# v2.net
KiCad netlist of a schematic drawn in EAGLE
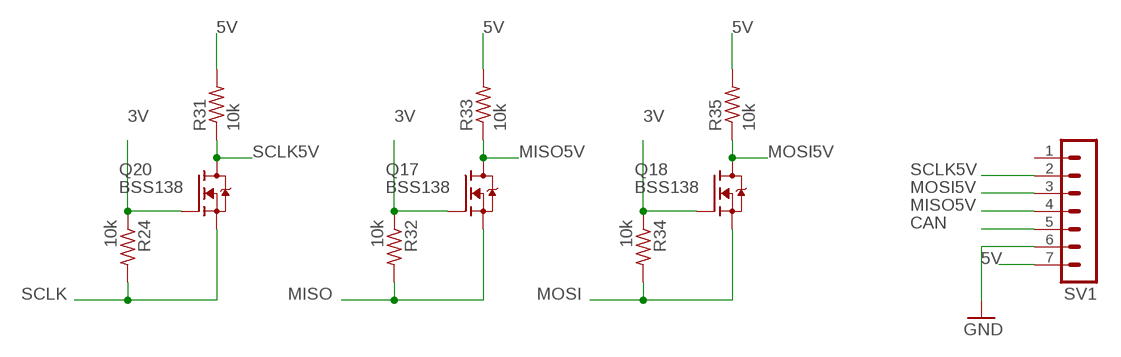
[diagram p0: schematic, sheet 1, part 1 of 2]
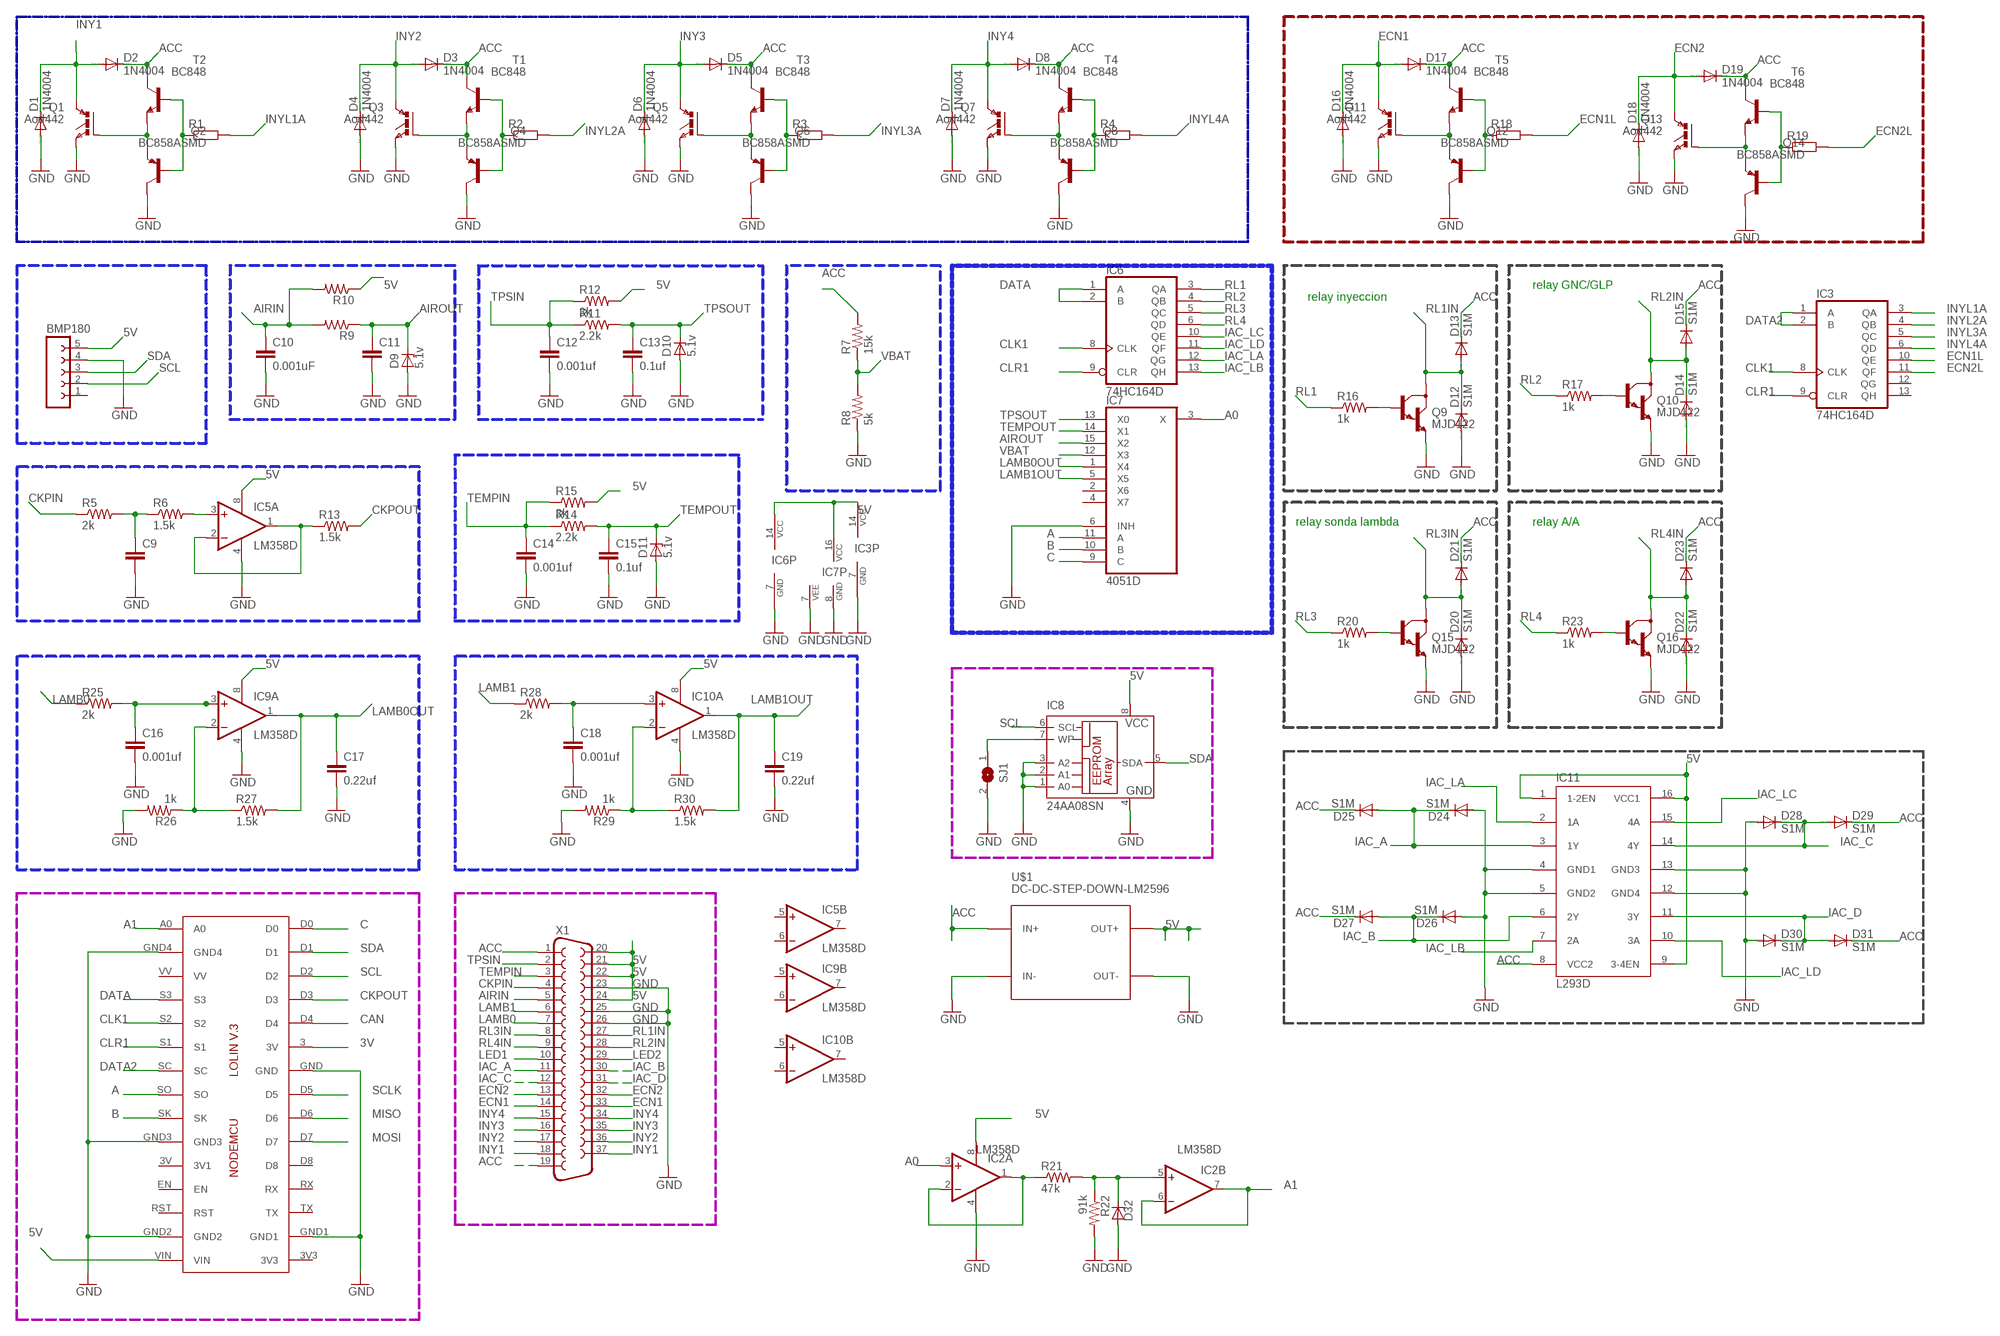
[diagram p1: schematic, sheet 1, part 2 of 2]

(export (version "E")
  (design (tool "Eeschema 10.0.6"))
  (components
    (comp (ref "BMP180")
      (value "FE05-1")
      (footprint "eagle-import:FE05-1")
      (libsource (lib "eagle-import") (part "FE05-1"))
    )
    (comp (ref "C9")
      (value "C-EU025-025X050")
      (footprint "eagle-import:C025-025X050")
      (libsource (lib "eagle-import") (part "C-EU025-025X050"))
    )
    (comp (ref "C10")
      (value "0.001uF")
      (footprint "eagle-import:C025-025X050")
      (libsource (lib "eagle-import") (part "C-EU025-025X050"))
    )
    (comp (ref "C11")
      (value "C-EU025-025X050")
      (footprint "eagle-import:C025-025X050")
      (libsource (lib "eagle-import") (part "C-EU025-025X050"))
    )
    (comp (ref "C12")
      (value "0.001uf")
      (footprint "eagle-import:C025-025X050")
      (libsource (lib "eagle-import") (part "C-EU025-025X050"))
    )
    (comp (ref "C13")
      (value "0.1uf")
      (footprint "eagle-import:C025-025X050")
      (libsource (lib "eagle-import") (part "C-EU025-025X050"))
    )
    (comp (ref "C14")
      (value "0.001uf")
      (footprint "eagle-import:C025-025X050")
      (libsource (lib "eagle-import") (part "C-EU025-025X050"))
    )
    (comp (ref "C15")
      (value "0.1uf")
      (footprint "eagle-import:C025-025X050")
      (libsource (lib "eagle-import") (part "C-EU025-025X050"))
    )
    (comp (ref "C16")
      (value "0.001uf")
      (footprint "eagle-import:C025-025X050")
      (libsource (lib "eagle-import") (part "C-EU025-025X050"))
    )
    (comp (ref "C17")
      (value "0.22uf")
      (footprint "eagle-import:C025-025X050")
      (libsource (lib "eagle-import") (part "C-EU025-025X050"))
    )
    (comp (ref "C18")
      (value "0.001uf")
      (footprint "eagle-import:C025-025X050")
      (libsource (lib "eagle-import") (part "C-EU025-025X050"))
    )
    (comp (ref "C19")
      (value "0.22uf")
      (footprint "eagle-import:C025-025X050")
      (libsource (lib "eagle-import") (part "C-EU025-025X050"))
    )
    (comp (ref "D1")
      (value "1N4004")
      (footprint "eagle-import:DO41-10")
      (libsource (lib "eagle-import") (part "1N4004"))
    )
    (comp (ref "D2")
      (value "1N4004")
      (footprint "eagle-import:DO41-10")
      (libsource (lib "eagle-import") (part "1N4004"))
    )
    (comp (ref "D3")
      (value "1N4004")
      (footprint "eagle-import:DO41-10")
      (libsource (lib "eagle-import") (part "1N4004"))
    )
    (comp (ref "D4")
      (value "1N4004")
      (footprint "eagle-import:DO41-10")
      (libsource (lib "eagle-import") (part "1N4004"))
    )
    (comp (ref "D5")
      (value "1N4004")
      (footprint "eagle-import:DO41-10")
      (libsource (lib "eagle-import") (part "1N4004"))
    )
    (comp (ref "D6")
      (value "1N4004")
      (footprint "eagle-import:DO41-10")
      (libsource (lib "eagle-import") (part "1N4004"))
    )
    (comp (ref "D7")
      (value "1N4004")
      (footprint "eagle-import:DO41-10")
      (libsource (lib "eagle-import") (part "1N4004"))
    )
    (comp (ref "D8")
      (value "1N4004")
      (footprint "eagle-import:DO41-10")
      (libsource (lib "eagle-import") (part "1N4004"))
    )
    (comp (ref "D9")
      (value "5.1v")
      (footprint "eagle-import:ZDIO-5")
      (libsource (lib "eagle-import") (part "ZENER-DIODEZD-5"))
    )
    (comp (ref "D10")
      (value "5.1v")
      (footprint "eagle-import:ZDIO-5")
      (libsource (lib "eagle-import") (part "ZENER-DIODEZD-5"))
    )
    (comp (ref "D11")
      (value "5.1v")
      (footprint "eagle-import:ZDIO-5")
      (libsource (lib "eagle-import") (part "ZENER-DIODEZD-5"))
    )
    (comp (ref "D12")
      (value "S1M")
      (footprint "eagle-import:SMA")
      (libsource (lib "eagle-import") (part "S1M"))
    )
    (comp (ref "D13")
      (value "S1M")
      (footprint "eagle-import:SMA")
      (libsource (lib "eagle-import") (part "S1M"))
    )
    (comp (ref "D14")
      (value "S1M")
      (footprint "eagle-import:SMA")
      (libsource (lib "eagle-import") (part "S1M"))
    )
    (comp (ref "D15")
      (value "S1M")
      (footprint "eagle-import:SMA")
      (libsource (lib "eagle-import") (part "S1M"))
    )
    (comp (ref "D16")
      (value "1N4004")
      (footprint "eagle-import:DO41-10")
      (libsource (lib "eagle-import") (part "1N4004"))
    )
    (comp (ref "D17")
      (value "1N4004")
      (footprint "eagle-import:DO41-10")
      (libsource (lib "eagle-import") (part "1N4004"))
    )
    (comp (ref "D18")
      (value "1N4004")
      (footprint "eagle-import:DO41-10")
      (libsource (lib "eagle-import") (part "1N4004"))
    )
    (comp (ref "D19")
      (value "1N4004")
      (footprint "eagle-import:DO41-10")
      (libsource (lib "eagle-import") (part "1N4004"))
    )
    (comp (ref "D20")
      (value "S1M")
      (footprint "eagle-import:SMA")
      (libsource (lib "eagle-import") (part "S1M"))
    )
    (comp (ref "D21")
      (value "S1M")
      (footprint "eagle-import:SMA")
      (libsource (lib "eagle-import") (part "S1M"))
    )
    (comp (ref "D22")
      (value "S1M")
      (footprint "eagle-import:SMA")
      (libsource (lib "eagle-import") (part "S1M"))
    )
    (comp (ref "D23")
      (value "S1M")
      (footprint "eagle-import:SMA")
      (libsource (lib "eagle-import") (part "S1M"))
    )
    (comp (ref "D24")
      (value "S1M")
      (footprint "eagle-import:SMA")
      (libsource (lib "eagle-import") (part "S1M"))
    )
    (comp (ref "D25")
      (value "S1M")
      (footprint "eagle-import:SMA")
      (libsource (lib "eagle-import") (part "S1M"))
    )
    (comp (ref "D26")
      (value "S1M")
      (footprint "eagle-import:SMA")
      (libsource (lib "eagle-import") (part "S1M"))
    )
    (comp (ref "D27")
      (value "S1M")
      (footprint "eagle-import:SMA")
      (libsource (lib "eagle-import") (part "S1M"))
    )
    (comp (ref "D28")
      (value "S1M")
      (footprint "eagle-import:SMA")
      (libsource (lib "eagle-import") (part "S1M"))
    )
    (comp (ref "D29")
      (value "S1M")
      (footprint "eagle-import:SMA")
      (libsource (lib "eagle-import") (part "S1M"))
    )
    (comp (ref "D30")
      (value "S1M")
      (footprint "eagle-import:SMA")
      (libsource (lib "eagle-import") (part "S1M"))
    )
    (comp (ref "D31")
      (value "S1M")
      (footprint "eagle-import:SMA")
      (libsource (lib "eagle-import") (part "S1M"))
    )
    (comp (ref "D32")
      (value "ZENER-DIODEZD-2.5")
      (footprint "eagle-import:ZDIO-2.5")
      (libsource (lib "eagle-import") (part "ZENER-DIODEZD-2.5"))
    )
    (comp (ref "IC1")
      (value "LOLINV3")
      (footprint "eagle-import:LOLINV3")
      (libsource (lib "eagle-import") (part "LOLINV3"))
    )
    (comp (ref "IC2")
      (value "LM358D")
      (footprint "eagle-import:SO08")
      (libsource (lib "eagle-import") (part "LM358D"))
    )
    (comp (ref "IC3")
      (value "74HC164D")
      (footprint "eagle-import:SO14")
      (libsource (lib "eagle-import") (part "74164DHC"))
    )
    (comp (ref "IC5")
      (value "LM358D")
      (footprint "eagle-import:SO08")
      (libsource (lib "eagle-import") (part "LM358D"))
    )
    (comp (ref "IC6")
      (value "74HC164D")
      (footprint "eagle-import:SO14")
      (libsource (lib "eagle-import") (part "74164DHC"))
    )
    (comp (ref "IC7")
      (value "4051D")
      (footprint "eagle-import:SO16")
      (libsource (lib "eagle-import") (part "4051D"))
    )
    (comp (ref "IC8")
      (value "24AA08SN")
      (footprint "eagle-import:SO-08")
      (fields (field (name "MF") "MICROCHIP") (field (name "MPN") "24AA08-I/SN"))
      (libsource (lib "eagle-import") (part "24SNAA08"))
    )
    (comp (ref "IC9")
      (value "LM358D")
      (footprint "eagle-import:SO08")
      (libsource (lib "eagle-import") (part "LM358D"))
    )
    (comp (ref "IC10")
      (value "LM358D")
      (footprint "eagle-import:SO08")
      (libsource (lib "eagle-import") (part "LM358D"))
    )
    (comp (ref "IC11")
      (value "L293D")
      (footprint "eagle-import:DIL16")
      (libsource (lib "eagle-import") (part "L293D"))
    )
    (comp (ref "Q1")
      (value "Aod442")
      (footprint "eagle-import:TO252")
      (libsource (lib "eagle-import") (part "IGBTTO252"))
    )
    (comp (ref "Q2")
      (value "BC858ASMD")
      (footprint "eagle-import:SOT23-BEC")
      (libsource (lib "eagle-import") (part "BC858SMDA"))
    )
    (comp (ref "Q3")
      (value "Aod442")
      (footprint "eagle-import:TO252")
      (libsource (lib "eagle-import") (part "IGBTTO252"))
    )
    (comp (ref "Q4")
      (value "BC858ASMD")
      (footprint "eagle-import:SOT23-BEC")
      (libsource (lib "eagle-import") (part "BC858SMDA"))
    )
    (comp (ref "Q5")
      (value "Aod442")
      (footprint "eagle-import:TO252")
      (libsource (lib "eagle-import") (part "IGBTTO252"))
    )
    (comp (ref "Q6")
      (value "BC858ASMD")
      (footprint "eagle-import:SOT23-BEC")
      (libsource (lib "eagle-import") (part "BC858SMDA"))
    )
    (comp (ref "Q7")
      (value "Aod442")
      (footprint "eagle-import:TO252")
      (libsource (lib "eagle-import") (part "IGBTTO252"))
    )
    (comp (ref "Q8")
      (value "BC858ASMD")
      (footprint "eagle-import:SOT23-BEC")
      (libsource (lib "eagle-import") (part "BC858SMDA"))
    )
    (comp (ref "Q9")
      (value "MJD122")
      (footprint "eagle-import:DPAK")
      (fields (field (name "MF") "STMicroelectronics"))
      (libsource (lib "eagle-import") (part "MJD122"))
    )
    (comp (ref "Q10")
      (value "MJD122")
      (footprint "eagle-import:DPAK")
      (fields (field (name "MF") "STMicroelectronics"))
      (libsource (lib "eagle-import") (part "MJD122"))
    )
    (comp (ref "Q11")
      (value "Aod442")
      (footprint "eagle-import:TO252")
      (libsource (lib "eagle-import") (part "IGBTTO252"))
    )
    (comp (ref "Q12")
      (value "BC858ASMD")
      (footprint "eagle-import:SOT23-BEC")
      (libsource (lib "eagle-import") (part "BC858SMDA"))
    )
    (comp (ref "Q13")
      (value "Aod442")
      (footprint "eagle-import:TO252")
      (libsource (lib "eagle-import") (part "IGBTTO252"))
    )
    (comp (ref "Q14")
      (value "BC858ASMD")
      (footprint "eagle-import:SOT23-BEC")
      (libsource (lib "eagle-import") (part "BC858SMDA"))
    )
    (comp (ref "Q15")
      (value "MJD122")
      (footprint "eagle-import:DPAK")
      (fields (field (name "MF") "STMicroelectronics"))
      (libsource (lib "eagle-import") (part "MJD122"))
    )
    (comp (ref "Q16")
      (value "MJD122")
      (footprint "eagle-import:DPAK")
      (fields (field (name "MF") "STMicroelectronics"))
      (libsource (lib "eagle-import") (part "MJD122"))
    )
    (comp (ref "Q17")
      (value "BSS138")
      (footprint "eagle-import:SOT23")
      (fields (field (name "MF") "Fairchild"))
      (libsource (lib "eagle-import") (part "BSS138"))
    )
    (comp (ref "Q18")
      (value "BSS138")
      (footprint "eagle-import:SOT23")
      (fields (field (name "MF") "Fairchild"))
      (libsource (lib "eagle-import") (part "BSS138"))
    )
    (comp (ref "Q20")
      (value "BSS138")
      (footprint "eagle-import:SOT23")
      (fields (field (name "MF") "Fairchild"))
      (libsource (lib "eagle-import") (part "BSS138"))
    )
    (comp (ref "R1")
      (value "R-EU_0204/7")
      (footprint "eagle-import:0204_7")
      (libsource (lib "eagle-import") (part "R-EU_0204/7"))
    )
    (comp (ref "R2")
      (value "R-EU_0204/7")
      (footprint "eagle-import:0204_7")
      (libsource (lib "eagle-import") (part "R-EU_0204/7"))
    )
    (comp (ref "R3")
      (value "R-EU_0204/7")
      (footprint "eagle-import:0204_7")
      (libsource (lib "eagle-import") (part "R-EU_0204/7"))
    )
    (comp (ref "R4")
      (value "R-EU_0204/7")
      (footprint "eagle-import:0204_7")
      (libsource (lib "eagle-import") (part "R-EU_0204/7"))
    )
    (comp (ref "R5")
      (value "2k")
      (footprint "eagle-import:0204_5")
      (libsource (lib "eagle-import") (part "R-US_0204/5"))
    )
    (comp (ref "R6")
      (value "1.5k")
      (footprint "eagle-import:0204_5")
      (libsource (lib "eagle-import") (part "R-US_0204/5"))
    )
    (comp (ref "R7")
      (value "15k")
      (footprint "eagle-import:0204_5")
      (libsource (lib "eagle-import") (part "R-US_0204/5"))
    )
    (comp (ref "R8")
      (value "5k")
      (footprint "eagle-import:0204_5")
      (libsource (lib "eagle-import") (part "R-US_0204/5"))
    )
    (comp (ref "R9")
      (value "R-US_0204/5")
      (footprint "eagle-import:0204_5")
      (libsource (lib "eagle-import") (part "R-US_0204/5"))
    )
    (comp (ref "R10")
      (value "R-US_0204/5")
      (footprint "eagle-import:0204_5")
      (libsource (lib "eagle-import") (part "R-US_0204/5"))
    )
    (comp (ref "R11")
      (value "2.2k")
      (footprint "eagle-import:0204_5")
      (libsource (lib "eagle-import") (part "R-US_0204/5"))
    )
    (comp (ref "R12")
      (value "3k")
      (footprint "eagle-import:0204_5")
      (libsource (lib "eagle-import") (part "R-US_0204/5"))
    )
    (comp (ref "R13")
      (value "1.5k")
      (footprint "eagle-import:0204_5")
      (libsource (lib "eagle-import") (part "R-US_0204/5"))
    )
    (comp (ref "R14")
      (value "2.2k")
      (footprint "eagle-import:0204_5")
      (libsource (lib "eagle-import") (part "R-US_0204/5"))
    )
    (comp (ref "R15")
      (value "3k")
      (footprint "eagle-import:0204_5")
      (libsource (lib "eagle-import") (part "R-US_0204/5"))
    )
    (comp (ref "R16")
      (value "1k")
      (footprint "eagle-import:0204_5")
      (libsource (lib "eagle-import") (part "R-US_0204/5"))
    )
    (comp (ref "R17")
      (value "1k")
      (footprint "eagle-import:0204_5")
      (libsource (lib "eagle-import") (part "R-US_0204/5"))
    )
    (comp (ref "R18")
      (value "R-EU_0204/7")
      (footprint "eagle-import:0204_7")
      (libsource (lib "eagle-import") (part "R-EU_0204/7"))
    )
    (comp (ref "R19")
      (value "R-EU_0204/7")
      (footprint "eagle-import:0204_7")
      (libsource (lib "eagle-import") (part "R-EU_0204/7"))
    )
    (comp (ref "R20")
      (value "1k")
      (footprint "eagle-import:0204_5")
      (libsource (lib "eagle-import") (part "R-US_0204/5"))
    )
    (comp (ref "R21")
      (value "47k")
      (footprint "eagle-import:0204_5")
      (libsource (lib "eagle-import") (part "R-US_0204/5"))
    )
    (comp (ref "R22")
      (value "91k")
      (footprint "eagle-import:0204_5")
      (libsource (lib "eagle-import") (part "R-US_0204/5"))
    )
    (comp (ref "R23")
      (value "1k")
      (footprint "eagle-import:0204_5")
      (libsource (lib "eagle-import") (part "R-US_0204/5"))
    )
    (comp (ref "R24")
      (value "10k")
      (footprint "eagle-import:0204_5")
      (libsource (lib "eagle-import") (part "R-US_0204/5"))
    )
    (comp (ref "R25")
      (value "2k")
      (footprint "eagle-import:0204_5")
      (libsource (lib "eagle-import") (part "R-US_0204/5"))
    )
    (comp (ref "R26")
      (value "1k")
      (footprint "eagle-import:0204_5")
      (libsource (lib "eagle-import") (part "R-US_0204/5"))
    )
    (comp (ref "R27")
      (value "1.5k")
      (footprint "eagle-import:0204_5")
      (libsource (lib "eagle-import") (part "R-US_0204/5"))
    )
    (comp (ref "R28")
      (value "2k")
      (footprint "eagle-import:0204_5")
      (libsource (lib "eagle-import") (part "R-US_0204/5"))
    )
    (comp (ref "R29")
      (value "1k")
      (footprint "eagle-import:0204_5")
      (libsource (lib "eagle-import") (part "R-US_0204/5"))
    )
    (comp (ref "R30")
      (value "1.5k")
      (footprint "eagle-import:0204_5")
      (libsource (lib "eagle-import") (part "R-US_0204/5"))
    )
    (comp (ref "R31")
      (value "10k")
      (footprint "eagle-import:0204_5")
      (libsource (lib "eagle-import") (part "R-US_0204/5"))
    )
    (comp (ref "R32")
      (value "10k")
      (footprint "eagle-import:0204_5")
      (libsource (lib "eagle-import") (part "R-US_0204/5"))
    )
    (comp (ref "R33")
      (value "10k")
      (footprint "eagle-import:0204_5")
      (libsource (lib "eagle-import") (part "R-US_0204/5"))
    )
    (comp (ref "R34")
      (value "10k")
      (footprint "eagle-import:0204_5")
      (libsource (lib "eagle-import") (part "R-US_0204/5"))
    )
    (comp (ref "R35")
      (value "10k")
      (footprint "eagle-import:0204_5")
      (libsource (lib "eagle-import") (part "R-US_0204/5"))
    )
    (comp (ref "SJ1")
      (value "SJW")
      (footprint "eagle-import:SJW")
      (libsource (lib "eagle-import") (part "SJW"))
    )
    (comp (ref "SV1")
      (value "MA07-1")
      (footprint "eagle-import:MA07-1")
      (libsource (lib "eagle-import") (part "MA07-1"))
    )
    (comp (ref "T1")
      (value "BC848")
      (footprint "eagle-import:SOT23")
      (libsource (lib "eagle-import") (part "BC848"))
    )
    (comp (ref "T2")
      (value "BC848")
      (footprint "eagle-import:SOT23")
      (libsource (lib "eagle-import") (part "BC848"))
    )
    (comp (ref "T3")
      (value "BC848")
      (footprint "eagle-import:SOT23")
      (libsource (lib "eagle-import") (part "BC848"))
    )
    (comp (ref "T4")
      (value "BC848")
      (footprint "eagle-import:SOT23")
      (libsource (lib "eagle-import") (part "BC848"))
    )
    (comp (ref "T5")
      (value "BC848")
      (footprint "eagle-import:SOT23")
      (libsource (lib "eagle-import") (part "BC848"))
    )
    (comp (ref "T6")
      (value "BC848")
      (footprint "eagle-import:SOT23")
      (libsource (lib "eagle-import") (part "BC848"))
    )
    (comp (ref "U$1")
      (value "DC-DC-STEP-DOWN-LM2596")
      (footprint "eagle-import:DC-DC-STEP-DOWN-LM2596")
      (libsource (lib "eagle-import") (part "DC-DC-STEP-DOWN-LM2596"))
    )
    (comp (ref "X1")
      (value "F37HP")
      (footprint "eagle-import:F37HP")
      (libsource (lib "eagle-import") (part "F37HP"))
    )
  )
  (nets
    (net (code "1") (name "/3V") (class "Default")
      (node (ref "IC1") (pin "3") (pinfunction "3V_3") (pintype "bidirectional"))
      (node (ref "Q17") (pin "1") (pinfunction "G_1") (pintype "passive"))
      (node (ref "Q18") (pin "1") (pinfunction "G_1") (pintype "passive"))
      (node (ref "Q20") (pin "1") (pinfunction "G_1") (pintype "passive"))
      (node (ref "R24") (pin "1") (pinfunction "1_1") (pintype "passive"))
      (node (ref "R32") (pin "1") (pinfunction "1_1") (pintype "passive"))
      (node (ref "R34") (pin "1") (pinfunction "1_1") (pintype "passive"))
    )
    (net (code "2") (name "/5V") (class "Default")
      (node (ref "BMP180") (pin "5") (pinfunction "5_5") (pintype "passive"))
      (node (ref "IC1") (pin "VIN") (pinfunction "VIN_VIN") (pintype "bidirectional"))
      (node (ref "IC10") (pin "8") (pinfunction "V+_8") (pintype "power_in"))
      (node (ref "IC11") (pin "1") (pinfunction "1-2EN_1") (pintype "input"))
      (node (ref "IC11") (pin "16") (pinfunction "VCC1_16") (pintype "power_in"))
      (node (ref "IC11") (pin "9") (pinfunction "3-4EN_9") (pintype "input"))
      (node (ref "IC2") (pin "8") (pinfunction "V+_8") (pintype "power_in"))
      (node (ref "IC3") (pin "14") (pinfunction "VCC_14") (pintype "power_in"))
      (node (ref "IC5") (pin "8") (pinfunction "V+_8") (pintype "power_in"))
      (node (ref "IC6") (pin "14") (pinfunction "VCC_14") (pintype "power_in"))
      (node (ref "IC7") (pin "16") (pinfunction "VCC_16") (pintype "power_in"))
      (node (ref "IC8") (pin "8") (pinfunction "VCC_8") (pintype "power_in"))
      (node (ref "IC9") (pin "8") (pinfunction "V+_8") (pintype "power_in"))
      (node (ref "R10") (pin "1") (pinfunction "1_1") (pintype "passive"))
      (node (ref "R12") (pin "2") (pinfunction "2_2") (pintype "passive"))
      (node (ref "R15") (pin "2") (pinfunction "2_2") (pintype "passive"))
      (node (ref "R31") (pin "2") (pinfunction "2_2") (pintype "passive"))
      (node (ref "R33") (pin "2") (pinfunction "2_2") (pintype "passive"))
      (node (ref "R35") (pin "2") (pinfunction "2_2") (pintype "passive"))
      (node (ref "SV1") (pin "7") (pinfunction "7_7") (pintype "passive"))
      (node (ref "U$1") (pin "OUT+") (pinfunction "OUT+_OUT+") (pintype "bidirectional"))
      (node (ref "X1") (pin "20") (pinfunction "20_20") (pintype "passive"))
      (node (ref "X1") (pin "21") (pinfunction "21_21") (pintype "passive"))
      (node (ref "X1") (pin "22") (pinfunction "22_22") (pintype "passive"))
      (node (ref "X1") (pin "24") (pinfunction "24_24") (pintype "passive"))
    )
    (net (code "3") (name "/A") (class "Default")
      (node (ref "IC1") (pin "SO") (pinfunction "SO_SO") (pintype "bidirectional"))
      (node (ref "IC7") (pin "11") (pinfunction "A_11") (pintype "input"))
    )
    (net (code "4") (name "/A0") (class "Default")
      (node (ref "IC2") (pin "3") (pinfunction "+IN_3") (pintype "input"))
      (node (ref "IC7") (pin "3") (pinfunction "X_3") (pintype "bidirectional"))
    )
    (net (code "5") (name "/A1") (class "Default")
      (node (ref "IC1") (pin "A0") (pinfunction "A0_A0") (pintype "bidirectional"))
      (node (ref "IC2") (pin "6") (pinfunction "-IN_6") (pintype "input"))
      (node (ref "IC2") (pin "7") (pinfunction "OUT_7") (pintype "output"))
    )
    (net (code "6") (name "/ACC") (class "Default")
      (node (ref "D13") (pin "C") (pinfunction "C_C") (pintype "passive"))
      (node (ref "D15") (pin "C") (pinfunction "C_C") (pintype "passive"))
      (node (ref "D17") (pin "C") (pinfunction "C_C") (pintype "passive"))
      (node (ref "D19") (pin "C") (pinfunction "C_C") (pintype "passive"))
      (node (ref "D2") (pin "C") (pinfunction "C_C") (pintype "passive"))
      (node (ref "D21") (pin "C") (pinfunction "C_C") (pintype "passive"))
      (node (ref "D23") (pin "C") (pinfunction "C_C") (pintype "passive"))
      (node (ref "D25") (pin "C") (pinfunction "C_C") (pintype "passive"))
      (node (ref "D27") (pin "C") (pinfunction "C_C") (pintype "passive"))
      (node (ref "D29") (pin "C") (pinfunction "C_C") (pintype "passive"))
      (node (ref "D3") (pin "C") (pinfunction "C_C") (pintype "passive"))
      (node (ref "D31") (pin "C") (pinfunction "C_C") (pintype "passive"))
      (node (ref "D5") (pin "C") (pinfunction "C_C") (pintype "passive"))
      (node (ref "D8") (pin "C") (pinfunction "C_C") (pintype "passive"))
      (node (ref "IC11") (pin "8") (pinfunction "VCC2_8") (pintype "power_in"))
      (node (ref "R7") (pin "2") (pinfunction "2_2") (pintype "passive"))
      (node (ref "T1") (pin "3") (pinfunction "C_3") (pintype "passive"))
      (node (ref "T2") (pin "3") (pinfunction "C_3") (pintype "passive"))
      (node (ref "T3") (pin "3") (pinfunction "C_3") (pintype "passive"))
      (node (ref "T4") (pin "3") (pinfunction "C_3") (pintype "passive"))
      (node (ref "T5") (pin "3") (pinfunction "C_3") (pintype "passive"))
      (node (ref "T6") (pin "3") (pinfunction "C_3") (pintype "passive"))
      (node (ref "U$1") (pin "IN+") (pinfunction "IN+_IN+") (pintype "bidirectional"))
      (node (ref "X1") (pin "1") (pinfunction "1_1") (pintype "passive"))
      (node (ref "X1") (pin "19") (pinfunction "19_19") (pintype "passive"))
    )
    (net (code "7") (name "/AIRIN") (class "Default")
      (node (ref "C10") (pin "1") (pinfunction "1_1") (pintype "passive"))
      (node (ref "R10") (pin "2") (pinfunction "2_2") (pintype "passive"))
      (node (ref "R9") (pin "2") (pinfunction "2_2") (pintype "passive"))
      (node (ref "X1") (pin "5") (pinfunction "5_5") (pintype "passive"))
    )
    (net (code "8") (name "/AIROUT") (class "Default")
      (node (ref "C11") (pin "1") (pinfunction "1_1") (pintype "passive"))
      (node (ref "D9") (pin "C") (pinfunction "C_C") (pintype "passive"))
      (node (ref "IC7") (pin "15") (pinfunction "X2_15") (pintype "bidirectional"))
      (node (ref "R9") (pin "1") (pinfunction "1_1") (pintype "passive"))
    )
    (net (code "9") (name "/B") (class "Default")
      (node (ref "IC1") (pin "SK") (pinfunction "SK_SK") (pintype "bidirectional"))
      (node (ref "IC7") (pin "10") (pinfunction "B_10") (pintype "input"))
    )
    (net (code "10") (name "/C") (class "Default")
      (node (ref "IC1") (pin "D0") (pinfunction "D0_D0") (pintype "bidirectional"))
      (node (ref "IC7") (pin "9") (pinfunction "C_9") (pintype "input"))
    )
    (net (code "11") (name "/CAN") (class "Default")
      (node (ref "IC1") (pin "D4") (pinfunction "D4_D4") (pintype "bidirectional"))
      (node (ref "SV1") (pin "5") (pinfunction "5_5") (pintype "passive"))
    )
    (net (code "12") (name "/CKPIN") (class "Default")
      (node (ref "R5") (pin "1") (pinfunction "1_1") (pintype "passive"))
      (node (ref "X1") (pin "4") (pinfunction "4_4") (pintype "passive"))
    )
    (net (code "13") (name "/CKPOUT") (class "Default")
      (node (ref "IC1") (pin "D3") (pinfunction "D3_D3") (pintype "bidirectional"))
      (node (ref "R13") (pin "2") (pinfunction "2_2") (pintype "passive"))
    )
    (net (code "14") (name "/CLK1") (class "Default")
      (node (ref "IC1") (pin "S2") (pinfunction "S2_S2") (pintype "bidirectional"))
      (node (ref "IC3") (pin "8") (pinfunction "CLK_8") (pintype "input"))
      (node (ref "IC6") (pin "8") (pinfunction "CLK_8") (pintype "input"))
    )
    (net (code "15") (name "/CLR1") (class "Default")
      (node (ref "IC1") (pin "S1") (pinfunction "S1_S1") (pintype "bidirectional"))
      (node (ref "IC3") (pin "9") (pinfunction "CLR_9") (pintype "input"))
      (node (ref "IC6") (pin "9") (pinfunction "CLR_9") (pintype "input"))
    )
    (net (code "16") (name "/DATA") (class "Default")
      (node (ref "IC1") (pin "S3") (pinfunction "S3_S3") (pintype "bidirectional"))
      (node (ref "IC6") (pin "1") (pinfunction "A_1") (pintype "input"))
      (node (ref "IC6") (pin "2") (pinfunction "B_2") (pintype "input"))
    )
    (net (code "17") (name "/DATA2") (class "Default")
      (node (ref "IC1") (pin "SC") (pinfunction "SC_SC") (pintype "bidirectional"))
      (node (ref "IC3") (pin "1") (pinfunction "A_1") (pintype "input"))
      (node (ref "IC3") (pin "2") (pinfunction "B_2") (pintype "input"))
    )
    (net (code "18") (name "/ECN1") (class "Default")
      (node (ref "D16") (pin "C") (pinfunction "C_C") (pintype "passive"))
      (node (ref "D17") (pin "A") (pinfunction "A_A") (pintype "passive"))
      (node (ref "Q11") (pin "2") (pinfunction "C_2") (pintype "passive"))
      (node (ref "X1") (pin "14") (pinfunction "14_14") (pintype "passive"))
      (node (ref "X1") (pin "33") (pinfunction "33_33") (pintype "passive"))
    )
    (net (code "19") (name "/ECN1L") (class "Default")
      (node (ref "IC3") (pin "10") (pinfunction "QE_10") (pintype "output"))
      (node (ref "R18") (pin "2") (pinfunction "2_2") (pintype "passive"))
    )
    (net (code "20") (name "/ECN2") (class "Default")
      (node (ref "D18") (pin "C") (pinfunction "C_C") (pintype "passive"))
      (node (ref "D19") (pin "A") (pinfunction "A_A") (pintype "passive"))
      (node (ref "Q13") (pin "2") (pinfunction "C_2") (pintype "passive"))
      (node (ref "X1") (pin "13") (pinfunction "13_13") (pintype "passive"))
      (node (ref "X1") (pin "32") (pinfunction "32_32") (pintype "passive"))
    )
    (net (code "21") (name "/ECN2L") (class "Default")
      (node (ref "IC3") (pin "11") (pinfunction "QF_11") (pintype "output"))
      (node (ref "R19") (pin "2") (pinfunction "2_2") (pintype "passive"))
    )
    (net (code "22") (name "/IAC_A") (class "Default")
      (node (ref "D24") (pin "C") (pinfunction "C_C") (pintype "passive"))
      (node (ref "D25") (pin "A") (pinfunction "A_A") (pintype "passive"))
      (node (ref "IC11") (pin "3") (pinfunction "1Y_3") (pintype "output"))
      (node (ref "X1") (pin "11") (pinfunction "11_11") (pintype "passive"))
    )
    (net (code "23") (name "/IAC_B") (class "Default")
      (node (ref "D26") (pin "C") (pinfunction "C_C") (pintype "passive"))
      (node (ref "D27") (pin "A") (pinfunction "A_A") (pintype "passive"))
      (node (ref "IC11") (pin "6") (pinfunction "2Y_6") (pintype "output"))
      (node (ref "X1") (pin "30") (pinfunction "30_30") (pintype "passive"))
    )
    (net (code "24") (name "/IAC_C") (class "Default")
      (node (ref "D28") (pin "C") (pinfunction "C_C") (pintype "passive"))
      (node (ref "D29") (pin "A") (pinfunction "A_A") (pintype "passive"))
      (node (ref "IC11") (pin "14") (pinfunction "4Y_14") (pintype "output"))
      (node (ref "X1") (pin "12") (pinfunction "12_12") (pintype "passive"))
    )
    (net (code "25") (name "/IAC_D") (class "Default")
      (node (ref "D30") (pin "C") (pinfunction "C_C") (pintype "passive"))
      (node (ref "D31") (pin "A") (pinfunction "A_A") (pintype "passive"))
      (node (ref "IC11") (pin "11") (pinfunction "3Y_11") (pintype "output"))
      (node (ref "X1") (pin "31") (pinfunction "31_31") (pintype "passive"))
    )
    (net (code "26") (name "/IAC_LA") (class "Default")
      (node (ref "IC11") (pin "2") (pinfunction "1A_2") (pintype "input"))
      (node (ref "IC6") (pin "12") (pinfunction "QG_12") (pintype "output"))
    )
    (net (code "27") (name "/IAC_LB") (class "Default")
      (node (ref "IC11") (pin "7") (pinfunction "2A_7") (pintype "input"))
      (node (ref "IC6") (pin "13") (pinfunction "QH_13") (pintype "output"))
    )
    (net (code "28") (name "/IAC_LC") (class "Default")
      (node (ref "IC11") (pin "15") (pinfunction "4A_15") (pintype "input"))
      (node (ref "IC6") (pin "10") (pinfunction "QE_10") (pintype "output"))
    )
    (net (code "29") (name "/IAC_LD") (class "Default")
      (node (ref "IC11") (pin "10") (pinfunction "3A_10") (pintype "input"))
      (node (ref "IC6") (pin "11") (pinfunction "QF_11") (pintype "output"))
    )
    (net (code "30") (name "/INY1") (class "Default")
      (node (ref "D1") (pin "C") (pinfunction "C_C") (pintype "passive"))
      (node (ref "D2") (pin "A") (pinfunction "A_A") (pintype "passive"))
      (node (ref "Q1") (pin "2") (pinfunction "C_2") (pintype "passive"))
      (node (ref "X1") (pin "18") (pinfunction "18_18") (pintype "passive"))
      (node (ref "X1") (pin "37") (pinfunction "37_37") (pintype "passive"))
    )
    (net (code "31") (name "/INY2") (class "Default")
      (node (ref "D3") (pin "A") (pinfunction "A_A") (pintype "passive"))
      (node (ref "D4") (pin "C") (pinfunction "C_C") (pintype "passive"))
      (node (ref "Q3") (pin "2") (pinfunction "C_2") (pintype "passive"))
      (node (ref "X1") (pin "17") (pinfunction "17_17") (pintype "passive"))
      (node (ref "X1") (pin "36") (pinfunction "36_36") (pintype "passive"))
    )
    (net (code "32") (name "/INY3") (class "Default")
      (node (ref "D5") (pin "A") (pinfunction "A_A") (pintype "passive"))
      (node (ref "D6") (pin "C") (pinfunction "C_C") (pintype "passive"))
      (node (ref "Q5") (pin "2") (pinfunction "C_2") (pintype "passive"))
      (node (ref "X1") (pin "16") (pinfunction "16_16") (pintype "passive"))
      (node (ref "X1") (pin "35") (pinfunction "35_35") (pintype "passive"))
    )
    (net (code "33") (name "/INY4") (class "Default")
      (node (ref "D7") (pin "C") (pinfunction "C_C") (pintype "passive"))
      (node (ref "D8") (pin "A") (pinfunction "A_A") (pintype "passive"))
      (node (ref "Q7") (pin "2") (pinfunction "C_2") (pintype "passive"))
      (node (ref "X1") (pin "15") (pinfunction "15_15") (pintype "passive"))
      (node (ref "X1") (pin "34") (pinfunction "34_34") (pintype "passive"))
    )
    (net (code "34") (name "/INYL1A") (class "Default")
      (node (ref "IC3") (pin "3") (pinfunction "QA_3") (pintype "output"))
      (node (ref "R1") (pin "2") (pinfunction "2_2") (pintype "passive"))
    )
    (net (code "35") (name "/INYL2A") (class "Default")
      (node (ref "IC3") (pin "4") (pinfunction "QB_4") (pintype "output"))
      (node (ref "R2") (pin "2") (pinfunction "2_2") (pintype "passive"))
    )
    (net (code "36") (name "/INYL3A") (class "Default")
      (node (ref "IC3") (pin "5") (pinfunction "QC_5") (pintype "output"))
      (node (ref "R3") (pin "2") (pinfunction "2_2") (pintype "passive"))
    )
    (net (code "37") (name "/INYL4A") (class "Default")
      (node (ref "IC3") (pin "6") (pinfunction "QD_6") (pintype "output"))
      (node (ref "R4") (pin "2") (pinfunction "2_2") (pintype "passive"))
    )
    (net (code "38") (name "/LAMB0") (class "Default")
      (node (ref "R25") (pin "1") (pinfunction "1_1") (pintype "passive"))
      (node (ref "X1") (pin "7") (pinfunction "7_7") (pintype "passive"))
    )
    (net (code "39") (name "/LAMB0OUT") (class "Default")
      (node (ref "C17") (pin "1") (pinfunction "1_1") (pintype "passive"))
      (node (ref "IC7") (pin "1") (pinfunction "X4_1") (pintype "bidirectional"))
      (node (ref "IC9") (pin "1") (pinfunction "OUT_1") (pintype "output"))
      (node (ref "R27") (pin "2") (pinfunction "2_2") (pintype "passive"))
    )
    (net (code "40") (name "/LAMB1") (class "Default")
      (node (ref "R28") (pin "1") (pinfunction "1_1") (pintype "passive"))
      (node (ref "X1") (pin "6") (pinfunction "6_6") (pintype "passive"))
    )
    (net (code "41") (name "/LAMB1OUT") (class "Default")
      (node (ref "C19") (pin "1") (pinfunction "1_1") (pintype "passive"))
      (node (ref "IC10") (pin "1") (pinfunction "OUT_1") (pintype "output"))
      (node (ref "IC7") (pin "5") (pinfunction "X5_5") (pintype "bidirectional"))
      (node (ref "R30") (pin "2") (pinfunction "2_2") (pintype "passive"))
    )
    (net (code "42") (name "/LED1") (class "Default")
      (node (ref "X1") (pin "10") (pinfunction "10_10") (pintype "passive"))
    )
    (net (code "43") (name "/LED2") (class "Default")
      (node (ref "X1") (pin "29") (pinfunction "29_29") (pintype "passive"))
    )
    (net (code "44") (name "/MISO") (class "Default")
      (node (ref "IC1") (pin "D6") (pinfunction "D6_D6") (pintype "bidirectional"))
      (node (ref "Q17") (pin "2") (pinfunction "S_2") (pintype "passive"))
      (node (ref "R32") (pin "2") (pinfunction "2_2") (pintype "passive"))
    )
    (net (code "45") (name "/MISO5V") (class "Default")
      (node (ref "Q17") (pin "3") (pinfunction "D_3") (pintype "passive"))
      (node (ref "R33") (pin "1") (pinfunction "1_1") (pintype "passive"))
      (node (ref "SV1") (pin "4") (pinfunction "4_4") (pintype "passive"))
    )
    (net (code "46") (name "/MOSI") (class "Default")
      (node (ref "IC1") (pin "D7") (pinfunction "D7_D7") (pintype "bidirectional"))
      (node (ref "Q18") (pin "2") (pinfunction "S_2") (pintype "passive"))
      (node (ref "R34") (pin "2") (pinfunction "2_2") (pintype "passive"))
    )
    (net (code "47") (name "/MOSI5V") (class "Default")
      (node (ref "Q18") (pin "3") (pinfunction "D_3") (pintype "passive"))
      (node (ref "R35") (pin "1") (pinfunction "1_1") (pintype "passive"))
      (node (ref "SV1") (pin "3") (pinfunction "3_3") (pintype "passive"))
    )
    (net (code "48") (name "/RL1") (class "Default")
      (node (ref "IC6") (pin "3") (pinfunction "QA_3") (pintype "output"))
      (node (ref "R16") (pin "1") (pinfunction "1_1") (pintype "passive"))
    )
    (net (code "49") (name "/RL1IN") (class "Default")
      (node (ref "D12") (pin "C") (pinfunction "C_C") (pintype "passive"))
      (node (ref "D13") (pin "A") (pinfunction "A_A") (pintype "passive"))
      (node (ref "Q9") (pin "4") (pinfunction "C_4") (pintype "passive"))
      (node (ref "X1") (pin "27") (pinfunction "27_27") (pintype "passive"))
    )
    (net (code "50") (name "/RL2") (class "Default")
      (node (ref "IC6") (pin "4") (pinfunction "QB_4") (pintype "output"))
      (node (ref "R17") (pin "1") (pinfunction "1_1") (pintype "passive"))
    )
    (net (code "51") (name "/RL2IN") (class "Default")
      (node (ref "D14") (pin "C") (pinfunction "C_C") (pintype "passive"))
      (node (ref "D15") (pin "A") (pinfunction "A_A") (pintype "passive"))
      (node (ref "Q10") (pin "4") (pinfunction "C_4") (pintype "passive"))
      (node (ref "X1") (pin "28") (pinfunction "28_28") (pintype "passive"))
    )
    (net (code "52") (name "/RL3") (class "Default")
      (node (ref "IC6") (pin "5") (pinfunction "QC_5") (pintype "output"))
      (node (ref "R20") (pin "1") (pinfunction "1_1") (pintype "passive"))
    )
    (net (code "53") (name "/RL3IN") (class "Default")
      (node (ref "D20") (pin "C") (pinfunction "C_C") (pintype "passive"))
      (node (ref "D21") (pin "A") (pinfunction "A_A") (pintype "passive"))
      (node (ref "Q15") (pin "4") (pinfunction "C_4") (pintype "passive"))
      (node (ref "X1") (pin "8") (pinfunction "8_8") (pintype "passive"))
    )
    (net (code "54") (name "/RL4") (class "Default")
      (node (ref "IC6") (pin "6") (pinfunction "QD_6") (pintype "output"))
      (node (ref "R23") (pin "1") (pinfunction "1_1") (pintype "passive"))
    )
    (net (code "55") (name "/RL4IN") (class "Default")
      (node (ref "D22") (pin "C") (pinfunction "C_C") (pintype "passive"))
      (node (ref "D23") (pin "A") (pinfunction "A_A") (pintype "passive"))
      (node (ref "Q16") (pin "4") (pinfunction "C_4") (pintype "passive"))
      (node (ref "X1") (pin "9") (pinfunction "9_9") (pintype "passive"))
    )
    (net (code "56") (name "/SCL") (class "Default")
      (node (ref "BMP180") (pin "2") (pinfunction "2_2") (pintype "passive"))
      (node (ref "IC1") (pin "D2") (pinfunction "D2_D2") (pintype "bidirectional"))
      (node (ref "IC8") (pin "6") (pinfunction "SCL_6") (pintype "input"))
    )
    (net (code "57") (name "/SCLK") (class "Default")
      (node (ref "IC1") (pin "D5") (pinfunction "D5_D5") (pintype "bidirectional"))
      (node (ref "Q20") (pin "2") (pinfunction "S_2") (pintype "passive"))
      (node (ref "R24") (pin "2") (pinfunction "2_2") (pintype "passive"))
    )
    (net (code "58") (name "/SCLK5V") (class "Default")
      (node (ref "Q20") (pin "3") (pinfunction "D_3") (pintype "passive"))
      (node (ref "R31") (pin "1") (pinfunction "1_1") (pintype "passive"))
      (node (ref "SV1") (pin "2") (pinfunction "2_2") (pintype "passive"))
    )
    (net (code "59") (name "/SDA") (class "Default")
      (node (ref "BMP180") (pin "3") (pinfunction "3_3") (pintype "passive"))
      (node (ref "IC1") (pin "D1") (pinfunction "D1_D1") (pintype "bidirectional"))
      (node (ref "IC8") (pin "5") (pinfunction "SDA_5") (pintype "bidirectional"))
    )
    (net (code "60") (name "/TEMPIN") (class "Default")
      (node (ref "C14") (pin "1") (pinfunction "1_1") (pintype "passive"))
      (node (ref "R14") (pin "1") (pinfunction "1_1") (pintype "passive"))
      (node (ref "R15") (pin "1") (pinfunction "1_1") (pintype "passive"))
      (node (ref "X1") (pin "3") (pinfunction "3_3") (pintype "passive"))
    )
    (net (code "61") (name "/TEMPOUT") (class "Default")
      (node (ref "C15") (pin "1") (pinfunction "1_1") (pintype "passive"))
      (node (ref "D11") (pin "C") (pinfunction "C_C") (pintype "passive"))
      (node (ref "IC7") (pin "14") (pinfunction "X1_14") (pintype "bidirectional"))
      (node (ref "R14") (pin "2") (pinfunction "2_2") (pintype "passive"))
    )
    (net (code "62") (name "/TPSIN") (class "Default")
      (node (ref "C12") (pin "1") (pinfunction "1_1") (pintype "passive"))
      (node (ref "R11") (pin "1") (pinfunction "1_1") (pintype "passive"))
      (node (ref "R12") (pin "1") (pinfunction "1_1") (pintype "passive"))
      (node (ref "X1") (pin "2") (pinfunction "2_2") (pintype "passive"))
    )
    (net (code "63") (name "/TPSOUT") (class "Default")
      (node (ref "C13") (pin "1") (pinfunction "1_1") (pintype "passive"))
      (node (ref "D10") (pin "C") (pinfunction "C_C") (pintype "passive"))
      (node (ref "IC7") (pin "13") (pinfunction "X0_13") (pintype "bidirectional"))
      (node (ref "R11") (pin "2") (pinfunction "2_2") (pintype "passive"))
    )
    (net (code "64") (name "/VBAT") (class "Default")
      (node (ref "IC7") (pin "12") (pinfunction "X3_12") (pintype "bidirectional"))
      (node (ref "R7") (pin "1") (pinfunction "1_1") (pintype "passive"))
      (node (ref "R8") (pin "2") (pinfunction "2_2") (pintype "passive"))
    )
    (net (code "65") (name "GND") (class "Default")
      (node (ref "BMP180") (pin "4") (pinfunction "4_4") (pintype "passive"))
      (node (ref "C10") (pin "2") (pinfunction "2_2") (pintype "passive"))
      (node (ref "C11") (pin "2") (pinfunction "2_2") (pintype "passive"))
      (node (ref "C12") (pin "2") (pinfunction "2_2") (pintype "passive"))
      (node (ref "C13") (pin "2") (pinfunction "2_2") (pintype "passive"))
      (node (ref "C14") (pin "2") (pinfunction "2_2") (pintype "passive"))
      (node (ref "C15") (pin "2") (pinfunction "2_2") (pintype "passive"))
      (node (ref "C16") (pin "2") (pinfunction "2_2") (pintype "passive"))
      (node (ref "C17") (pin "2") (pinfunction "2_2") (pintype "passive"))
      (node (ref "C18") (pin "2") (pinfunction "2_2") (pintype "passive"))
      (node (ref "C19") (pin "2") (pinfunction "2_2") (pintype "passive"))
      (node (ref "C9") (pin "2") (pinfunction "2_2") (pintype "passive"))
      (node (ref "D1") (pin "A") (pinfunction "A_A") (pintype "passive"))
      (node (ref "D10") (pin "A") (pinfunction "A_A") (pintype "passive"))
      (node (ref "D11") (pin "A") (pinfunction "A_A") (pintype "passive"))
      (node (ref "D12") (pin "A") (pinfunction "A_A") (pintype "passive"))
      (node (ref "D14") (pin "A") (pinfunction "A_A") (pintype "passive"))
      (node (ref "D16") (pin "A") (pinfunction "A_A") (pintype "passive"))
      (node (ref "D18") (pin "A") (pinfunction "A_A") (pintype "passive"))
      (node (ref "D20") (pin "A") (pinfunction "A_A") (pintype "passive"))
      (node (ref "D22") (pin "A") (pinfunction "A_A") (pintype "passive"))
      (node (ref "D24") (pin "A") (pinfunction "A_A") (pintype "passive"))
      (node (ref "D26") (pin "A") (pinfunction "A_A") (pintype "passive"))
      (node (ref "D28") (pin "A") (pinfunction "A_A") (pintype "passive"))
      (node (ref "D30") (pin "A") (pinfunction "A_A") (pintype "passive"))
      (node (ref "D32") (pin "A") (pinfunction "A_A") (pintype "passive"))
      (node (ref "D4") (pin "A") (pinfunction "A_A") (pintype "passive"))
      (node (ref "D6") (pin "A") (pinfunction "A_A") (pintype "passive"))
      (node (ref "D7") (pin "A") (pinfunction "A_A") (pintype "passive"))
      (node (ref "D9") (pin "A") (pinfunction "A_A") (pintype "passive"))
      (node (ref "IC1") (pin "GND") (pinfunction "GND_GND") (pintype "bidirectional"))
      (node (ref "IC1") (pin "GND1") (pinfunction "GND1_GND1") (pintype "bidirectional"))
      (node (ref "IC1") (pin "GND2") (pinfunction "GND2_GND2") (pintype "bidirectional"))
      (node (ref "IC1") (pin "GND3") (pinfunction "GND3_GND3") (pintype "bidirectional"))
      (node (ref "IC1") (pin "GND4") (pinfunction "GND4_GND4") (pintype "bidirectional"))
      (node (ref "IC10") (pin "4") (pinfunction "V-_4") (pintype "power_in"))
      (node (ref "IC11") (pin "12") (pinfunction "GND4_12") (pintype "power_in"))
      (node (ref "IC11") (pin "13") (pinfunction "GND3_13") (pintype "power_in"))
      (node (ref "IC11") (pin "4") (pinfunction "GND1_4") (pintype "power_in"))
      (node (ref "IC11") (pin "5") (pinfunction "GND2_5") (pintype "power_in"))
      (node (ref "IC2") (pin "4") (pinfunction "V-_4") (pintype "power_in"))
      (node (ref "IC3") (pin "7") (pinfunction "GND_7") (pintype "power_in"))
      (node (ref "IC5") (pin "4") (pinfunction "V-_4") (pintype "power_in"))
      (node (ref "IC6") (pin "7") (pinfunction "GND_7") (pintype "power_in"))
      (node (ref "IC7") (pin "6") (pinfunction "INH_6") (pintype "input"))
      (node (ref "IC7") (pin "7") (pinfunction "VEE_7") (pintype "power_in"))
      (node (ref "IC7") (pin "8") (pinfunction "GND_8") (pintype "power_in"))
      (node (ref "IC8") (pin "1") (pinfunction "A0_1") (pintype "input"))
      (node (ref "IC8") (pin "2") (pinfunction "A1_2") (pintype "input"))
      (node (ref "IC8") (pin "3") (pinfunction "A2_3") (pintype "input"))
      (node (ref "IC8") (pin "4") (pinfunction "GND_4") (pintype "power_in"))
      (node (ref "IC9") (pin "4") (pinfunction "V-_4") (pintype "power_in"))
      (node (ref "Q1") (pin "3") (pinfunction "E_3") (pintype "passive"))
      (node (ref "Q10") (pin "3") (pinfunction "E_3") (pintype "passive"))
      (node (ref "Q11") (pin "3") (pinfunction "E_3") (pintype "passive"))
      (node (ref "Q12") (pin "C") (pinfunction "C_C") (pintype "passive"))
      (node (ref "Q13") (pin "3") (pinfunction "E_3") (pintype "passive"))
      (node (ref "Q14") (pin "C") (pinfunction "C_C") (pintype "passive"))
      (node (ref "Q15") (pin "3") (pinfunction "E_3") (pintype "passive"))
      (node (ref "Q16") (pin "3") (pinfunction "E_3") (pintype "passive"))
      (node (ref "Q2") (pin "C") (pinfunction "C_C") (pintype "passive"))
      (node (ref "Q3") (pin "3") (pinfunction "E_3") (pintype "passive"))
      (node (ref "Q4") (pin "C") (pinfunction "C_C") (pintype "passive"))
      (node (ref "Q5") (pin "3") (pinfunction "E_3") (pintype "passive"))
      (node (ref "Q6") (pin "C") (pinfunction "C_C") (pintype "passive"))
      (node (ref "Q7") (pin "3") (pinfunction "E_3") (pintype "passive"))
      (node (ref "Q8") (pin "C") (pinfunction "C_C") (pintype "passive"))
      (node (ref "Q9") (pin "3") (pinfunction "E_3") (pintype "passive"))
      (node (ref "R22") (pin "2") (pinfunction "2_2") (pintype "passive"))
      (node (ref "R26") (pin "2") (pinfunction "2_2") (pintype "passive"))
      (node (ref "R29") (pin "2") (pinfunction "2_2") (pintype "passive"))
      (node (ref "R8") (pin "1") (pinfunction "1_1") (pintype "passive"))
      (node (ref "SJ1") (pin "2") (pinfunction "2_2") (pintype "passive"))
      (node (ref "SV1") (pin "6") (pinfunction "6_6") (pintype "passive"))
      (node (ref "U$1") (pin "IN-") (pinfunction "IN-_IN-") (pintype "bidirectional"))
      (node (ref "U$1") (pin "OUT-") (pinfunction "OUT-_OUT-") (pintype "bidirectional"))
      (node (ref "X1") (pin "23") (pinfunction "23_23") (pintype "passive"))
      (node (ref "X1") (pin "25") (pinfunction "25_25") (pintype "passive"))
      (node (ref "X1") (pin "26") (pinfunction "26_26") (pintype "passive"))
    )
    (net (code "66") (name "Net-(C9-Pad1)") (class "Default")
      (node (ref "C9") (pin "1") (pinfunction "1_1") (pintype "passive"))
      (node (ref "R5") (pin "2") (pinfunction "2_2") (pintype "passive"))
      (node (ref "R6") (pin "1") (pinfunction "1_1") (pintype "passive"))
    )
    (net (code "67") (name "Net-(IC2A--IN)") (class "Default")
      (node (ref "IC2") (pin "1") (pinfunction "OUT_1") (pintype "output"))
      (node (ref "IC2") (pin "2") (pinfunction "-IN_2") (pintype "input"))
      (node (ref "R21") (pin "1") (pinfunction "1_1") (pintype "passive"))
    )
    (net (code "68") (name "Net-(IC2B-+IN)") (class "Default")
      (node (ref "D32") (pin "C") (pinfunction "C_C") (pintype "passive"))
      (node (ref "IC2") (pin "5") (pinfunction "+IN_5") (pintype "input"))
      (node (ref "R21") (pin "2") (pinfunction "2_2") (pintype "passive"))
      (node (ref "R22") (pin "1") (pinfunction "1_1") (pintype "passive"))
    )
    (net (code "69") (name "Net-(IC5A-+IN)") (class "Default")
      (node (ref "IC5") (pin "3") (pinfunction "+IN_3") (pintype "input"))
      (node (ref "R6") (pin "2") (pinfunction "2_2") (pintype "passive"))
    )
    (net (code "70") (name "Net-(IC5A--IN)") (class "Default")
      (node (ref "IC5") (pin "1") (pinfunction "OUT_1") (pintype "output"))
      (node (ref "IC5") (pin "2") (pinfunction "-IN_2") (pintype "input"))
      (node (ref "R13") (pin "1") (pinfunction "1_1") (pintype "passive"))
    )
    (net (code "71") (name "Net-(IC8-WP)") (class "Default")
      (node (ref "IC8") (pin "7") (pinfunction "WP_7") (pintype "input"))
      (node (ref "SJ1") (pin "1") (pinfunction "1_1") (pintype "passive"))
    )
    (net (code "72") (name "Net-(IC9A-+IN)") (class "Default")
      (node (ref "C16") (pin "1") (pinfunction "1_1") (pintype "passive"))
      (node (ref "IC9") (pin "3") (pinfunction "+IN_3") (pintype "input"))
      (node (ref "R25") (pin "2") (pinfunction "2_2") (pintype "passive"))
    )
    (net (code "73") (name "Net-(IC9A--IN)") (class "Default")
      (node (ref "IC9") (pin "2") (pinfunction "-IN_2") (pintype "input"))
      (node (ref "R26") (pin "1") (pinfunction "1_1") (pintype "passive"))
      (node (ref "R27") (pin "1") (pinfunction "1_1") (pintype "passive"))
    )
    (net (code "74") (name "Net-(IC10A-+IN)") (class "Default")
      (node (ref "C18") (pin "1") (pinfunction "1_1") (pintype "passive"))
      (node (ref "IC10") (pin "3") (pinfunction "+IN_3") (pintype "input"))
      (node (ref "R28") (pin "2") (pinfunction "2_2") (pintype "passive"))
    )
    (net (code "75") (name "Net-(IC10A--IN)") (class "Default")
      (node (ref "IC10") (pin "2") (pinfunction "-IN_2") (pintype "input"))
      (node (ref "R29") (pin "1") (pinfunction "1_1") (pintype "passive"))
      (node (ref "R30") (pin "1") (pinfunction "1_1") (pintype "passive"))
    )
    (net (code "76") (name "Net-(Q1-G)") (class "Default")
      (node (ref "Q1") (pin "1") (pinfunction "G_1") (pintype "passive"))
      (node (ref "Q2") (pin "E") (pinfunction "E_E") (pintype "passive"))
      (node (ref "T2") (pin "2") (pinfunction "E_2") (pintype "passive"))
    )
    (net (code "77") (name "Net-(Q3-G)") (class "Default")
      (node (ref "Q3") (pin "1") (pinfunction "G_1") (pintype "passive"))
      (node (ref "Q4") (pin "E") (pinfunction "E_E") (pintype "passive"))
      (node (ref "T1") (pin "2") (pinfunction "E_2") (pintype "passive"))
    )
    (net (code "78") (name "Net-(Q5-G)") (class "Default")
      (node (ref "Q5") (pin "1") (pinfunction "G_1") (pintype "passive"))
      (node (ref "Q6") (pin "E") (pinfunction "E_E") (pintype "passive"))
      (node (ref "T3") (pin "2") (pinfunction "E_2") (pintype "passive"))
    )
    (net (code "79") (name "Net-(Q7-G)") (class "Default")
      (node (ref "Q7") (pin "1") (pinfunction "G_1") (pintype "passive"))
      (node (ref "Q8") (pin "E") (pinfunction "E_E") (pintype "passive"))
      (node (ref "T4") (pin "2") (pinfunction "E_2") (pintype "passive"))
    )
    (net (code "80") (name "Net-(Q9-B)") (class "Default")
      (node (ref "Q9") (pin "1") (pinfunction "B_1") (pintype "passive"))
      (node (ref "R16") (pin "2") (pinfunction "2_2") (pintype "passive"))
    )
    (net (code "81") (name "Net-(Q10-B)") (class "Default")
      (node (ref "Q10") (pin "1") (pinfunction "B_1") (pintype "passive"))
      (node (ref "R17") (pin "2") (pinfunction "2_2") (pintype "passive"))
    )
    (net (code "82") (name "Net-(Q11-G)") (class "Default")
      (node (ref "Q11") (pin "1") (pinfunction "G_1") (pintype "passive"))
      (node (ref "Q12") (pin "E") (pinfunction "E_E") (pintype "passive"))
      (node (ref "T5") (pin "2") (pinfunction "E_2") (pintype "passive"))
    )
    (net (code "83") (name "Net-(Q13-G)") (class "Default")
      (node (ref "Q13") (pin "1") (pinfunction "G_1") (pintype "passive"))
      (node (ref "Q14") (pin "E") (pinfunction "E_E") (pintype "passive"))
      (node (ref "T6") (pin "2") (pinfunction "E_2") (pintype "passive"))
    )
    (net (code "84") (name "Net-(Q15-B)") (class "Default")
      (node (ref "Q15") (pin "1") (pinfunction "B_1") (pintype "passive"))
      (node (ref "R20") (pin "2") (pinfunction "2_2") (pintype "passive"))
    )
    (net (code "85") (name "Net-(Q16-B)") (class "Default")
      (node (ref "Q16") (pin "1") (pinfunction "B_1") (pintype "passive"))
      (node (ref "R23") (pin "2") (pinfunction "2_2") (pintype "passive"))
    )
    (net (code "86") (name "Net-(T1-B)") (class "Default")
      (node (ref "Q4") (pin "B") (pinfunction "B_B") (pintype "passive"))
      (node (ref "R2") (pin "1") (pinfunction "1_1") (pintype "passive"))
      (node (ref "T1") (pin "1") (pinfunction "B_1") (pintype "passive"))
    )
    (net (code "87") (name "Net-(T2-B)") (class "Default")
      (node (ref "Q2") (pin "B") (pinfunction "B_B") (pintype "passive"))
      (node (ref "R1") (pin "1") (pinfunction "1_1") (pintype "passive"))
      (node (ref "T2") (pin "1") (pinfunction "B_1") (pintype "passive"))
    )
    (net (code "88") (name "Net-(T3-B)") (class "Default")
      (node (ref "Q6") (pin "B") (pinfunction "B_B") (pintype "passive"))
      (node (ref "R3") (pin "1") (pinfunction "1_1") (pintype "passive"))
      (node (ref "T3") (pin "1") (pinfunction "B_1") (pintype "passive"))
    )
    (net (code "89") (name "Net-(T4-B)") (class "Default")
      (node (ref "Q8") (pin "B") (pinfunction "B_B") (pintype "passive"))
      (node (ref "R4") (pin "1") (pinfunction "1_1") (pintype "passive"))
      (node (ref "T4") (pin "1") (pinfunction "B_1") (pintype "passive"))
    )
    (net (code "90") (name "Net-(T5-B)") (class "Default")
      (node (ref "Q12") (pin "B") (pinfunction "B_B") (pintype "passive"))
      (node (ref "R18") (pin "1") (pinfunction "1_1") (pintype "passive"))
      (node (ref "T5") (pin "1") (pinfunction "B_1") (pintype "passive"))
    )
    (net (code "91") (name "Net-(T6-B)") (class "Default")
      (node (ref "Q14") (pin "B") (pinfunction "B_B") (pintype "passive"))
      (node (ref "R19") (pin "1") (pinfunction "1_1") (pintype "passive"))
      (node (ref "T6") (pin "1") (pinfunction "B_1") (pintype "passive"))
    )
    (net (code "92") (name "unconnected-(BMP180-Pad1)") (class "Default")
      (node (ref "BMP180") (pin "1") (pinfunction "1_1") (pintype "passive"))
    )
    (net (code "93") (name "unconnected-(IC1-3V1-Pad3V)") (class "Default")
      (node (ref "IC1") (pin "3V") (pinfunction "3V1_3V") (pintype "bidirectional"))
    )
    (net (code "94") (name "unconnected-(IC1-Pad3V3)") (class "Default")
      (node (ref "IC1") (pin "3V3") (pinfunction "3V3_3V3") (pintype "bidirectional"))
    )
    (net (code "95") (name "unconnected-(IC1-PadD8)") (class "Default")
      (node (ref "IC1") (pin "D8") (pinfunction "D8_D8") (pintype "bidirectional"))
    )
    (net (code "96") (name "unconnected-(IC1-PadEN)") (class "Default")
      (node (ref "IC1") (pin "EN") (pinfunction "EN_EN") (pintype "bidirectional"))
    )
    (net (code "97") (name "unconnected-(IC1-PadRST)") (class "Default")
      (node (ref "IC1") (pin "RST") (pinfunction "RST_RST") (pintype "bidirectional"))
    )
    (net (code "98") (name "unconnected-(IC1-PadRX)") (class "Default")
      (node (ref "IC1") (pin "RX") (pinfunction "RX_RX") (pintype "bidirectional"))
    )
    (net (code "99") (name "unconnected-(IC1-PadTX)") (class "Default")
      (node (ref "IC1") (pin "TX") (pinfunction "TX_TX") (pintype "bidirectional"))
    )
    (net (code "100") (name "unconnected-(IC1-PadVV)") (class "Default")
      (node (ref "IC1") (pin "VV") (pinfunction "VV_VV") (pintype "bidirectional"))
    )
    (net (code "101") (name "unconnected-(IC3A-QG-Pad12)") (class "Default")
      (node (ref "IC3") (pin "12") (pinfunction "QG_12") (pintype "output"))
    )
    (net (code "102") (name "unconnected-(IC3A-QH-Pad13)") (class "Default")
      (node (ref "IC3") (pin "13") (pinfunction "QH_13") (pintype "output"))
    )
    (net (code "103") (name "unconnected-(IC5B-+IN-Pad5)") (class "Default")
      (node (ref "IC5") (pin "5") (pinfunction "+IN_5") (pintype "input"))
    )
    (net (code "104") (name "unconnected-(IC5B--IN-Pad6)") (class "Default")
      (node (ref "IC5") (pin "6") (pinfunction "-IN_6") (pintype "input"))
    )
    (net (code "105") (name "unconnected-(IC5B-OUT-Pad7)") (class "Default")
      (node (ref "IC5") (pin "7") (pinfunction "OUT_7") (pintype "output"))
    )
    (net (code "106") (name "unconnected-(IC7A-X6-Pad2)") (class "Default")
      (node (ref "IC7") (pin "2") (pinfunction "X6_2") (pintype "bidirectional"))
    )
    (net (code "107") (name "unconnected-(IC7A-X7-Pad4)") (class "Default")
      (node (ref "IC7") (pin "4") (pinfunction "X7_4") (pintype "bidirectional"))
    )
    (net (code "108") (name "unconnected-(IC9B-+IN-Pad5)") (class "Default")
      (node (ref "IC9") (pin "5") (pinfunction "+IN_5") (pintype "input"))
    )
    (net (code "109") (name "unconnected-(IC9B--IN-Pad6)") (class "Default")
      (node (ref "IC9") (pin "6") (pinfunction "-IN_6") (pintype "input"))
    )
    (net (code "110") (name "unconnected-(IC9B-OUT-Pad7)") (class "Default")
      (node (ref "IC9") (pin "7") (pinfunction "OUT_7") (pintype "output"))
    )
    (net (code "111") (name "unconnected-(IC10B-+IN-Pad5)") (class "Default")
      (node (ref "IC10") (pin "5") (pinfunction "+IN_5") (pintype "input"))
    )
    (net (code "112") (name "unconnected-(IC10B--IN-Pad6)") (class "Default")
      (node (ref "IC10") (pin "6") (pinfunction "-IN_6") (pintype "input"))
    )
    (net (code "113") (name "unconnected-(IC10B-OUT-Pad7)") (class "Default")
      (node (ref "IC10") (pin "7") (pinfunction "OUT_7") (pintype "output"))
    )
    (net (code "114") (name "unconnected-(SV1-Pad1)") (class "Default")
      (node (ref "SV1") (pin "1") (pinfunction "1_1") (pintype "passive"))
    )
  )
)
